# Interface_PCB.net
KiCad netlist of a schematic drawn in EAGLE
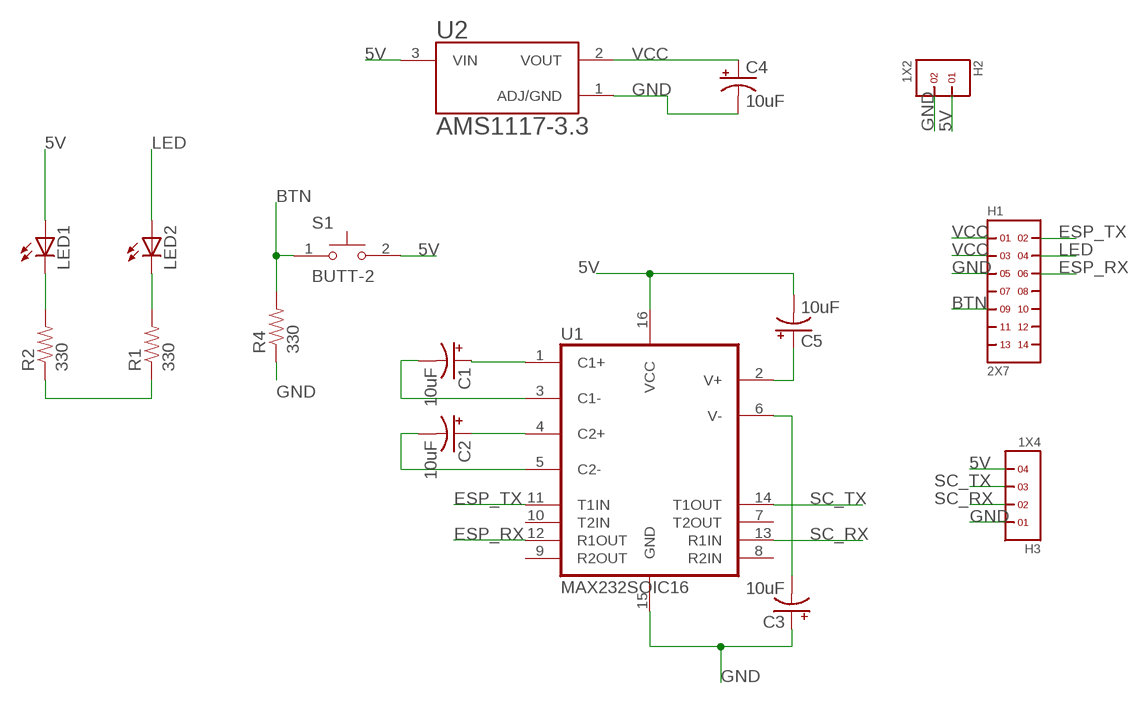
[diagram p0: schematic, sheet 1]

(export (version "E")
  (design (tool "Eeschema 10.0.6"))
  (components
    (comp (ref "C1")
      (value "10uF")
      (footprint "eagle-import:EIA3216")
      (libsource (lib "eagle-import") (part "10UF-16V-10%(TANT)"))
    )
    (comp (ref "C2")
      (value "10uF")
      (footprint "eagle-import:EIA3216")
      (libsource (lib "eagle-import") (part "10UF-16V-10%(TANT)"))
    )
    (comp (ref "C3")
      (value "10uF")
      (footprint "eagle-import:EIA3216")
      (libsource (lib "eagle-import") (part "10UF-16V-10%(TANT)"))
    )
    (comp (ref "C4")
      (value "10uF")
      (footprint "eagle-import:EIA3216")
      (libsource (lib "eagle-import") (part "10UF-16V-10%(TANT)"))
    )
    (comp (ref "C5")
      (value "10uF")
      (footprint "eagle-import:EIA3216")
      (libsource (lib "eagle-import") (part "10UF-16V-10%(TANT)"))
    )
    (comp (ref "H1")
      (value "2X7")
      (footprint "eagle-import:2X7")
      (libsource (lib "eagle-import") (part "2X7"))
    )
    (comp (ref "H2")
      (value "1X2")
      (footprint "eagle-import:1X2")
      (libsource (lib "eagle-import") (part "1X2"))
    )
    (comp (ref "H3")
      (value "1X4")
      (footprint "eagle-import:1X4")
      (libsource (lib "eagle-import") (part "1X4"))
    )
    (comp (ref "LED1")
      (value "LED5MM")
      (footprint "eagle-import:LED5MM")
      (libsource (lib "eagle-import") (part "LED5MM"))
    )
    (comp (ref "LED2")
      (value "LED5MM")
      (footprint "eagle-import:LED5MM")
      (libsource (lib "eagle-import") (part "LED5MM"))
    )
    (comp (ref "R1")
      (value "330")
      (footprint "eagle-import:0402-RES")
      (libsource (lib "eagle-import") (part "RESISTOR0402-RES"))
    )
    (comp (ref "R2")
      (value "330")
      (footprint "eagle-import:0402-RES")
      (libsource (lib "eagle-import") (part "RESISTOR0402-RES"))
    )
    (comp (ref "R4")
      (value "330")
      (footprint "eagle-import:0402-RES")
      (libsource (lib "eagle-import") (part "RESISTOR0402-RES"))
    )
    (comp (ref "S1")
      (value "BUTT-2")
      (footprint "eagle-import:SW_BUTT-2")
      (fields (field (name "MF") "Gravitech"))
      (libsource (lib "eagle-import") (part "BUTT-2"))
    )
    (comp (ref "U1")
      (value "MAX232SOIC16")
      (footprint "eagle-import:SO016")
      (libsource (lib "eagle-import") (part "MAX232SOIC16"))
    )
    (comp (ref "U2")
      (value "AMS1117-3.3")
      (footprint "eagle-import:SOT229P700X180-4N")
      (fields (field (name "MF") "Advanced Monolithic Systems"))
      (libsource (lib "eagle-import") (part "AMS1117-3.3"))
    )
  )
  (nets
    (net (code "1") (name "/5V") (class "Default")
      (node (ref "C5") (pin "C") (pinfunction "-_C") (pintype "passive"))
      (node (ref "H2") (pin "1") (pinfunction "1_1") (pintype "bidirectional"))
      (node (ref "H3") (pin "4") (pinfunction "4_4") (pintype "bidirectional"))
      (node (ref "LED1") (pin "A") (pinfunction "A_A") (pintype "passive"))
      (node (ref "S1") (pin "2") (pinfunction "2_2") (pintype "passive"))
      (node (ref "U1") (pin "16") (pinfunction "VCC_16") (pintype "bidirectional"))
      (node (ref "U2") (pin "3") (pinfunction "VIN_3") (pintype "input"))
    )
    (net (code "2") (name "/BTN") (class "Default")
      (node (ref "H1") (pin "9") (pinfunction "9_9") (pintype "bidirectional"))
      (node (ref "R4") (pin "2") (pinfunction "2_2") (pintype "passive"))
      (node (ref "S1") (pin "1") (pinfunction "1_1") (pintype "passive"))
    )
    (net (code "3") (name "/ESP_RX") (class "Default")
      (node (ref "H1") (pin "6") (pinfunction "6_6") (pintype "bidirectional"))
      (node (ref "U1") (pin "12") (pinfunction "R1OUT_12") (pintype "output"))
    )
    (net (code "4") (name "/ESP_TX") (class "Default")
      (node (ref "H1") (pin "2") (pinfunction "2_2") (pintype "bidirectional"))
      (node (ref "U1") (pin "11") (pinfunction "T1IN_11") (pintype "input"))
    )
    (net (code "5") (name "/GND") (class "Default")
      (node (ref "C3") (pin "A") (pinfunction "+_A") (pintype "passive"))
      (node (ref "C4") (pin "C") (pinfunction "-_C") (pintype "passive"))
      (node (ref "H1") (pin "5") (pinfunction "5_5") (pintype "bidirectional"))
      (node (ref "H2") (pin "2") (pinfunction "2_2") (pintype "bidirectional"))
      (node (ref "H3") (pin "1") (pinfunction "1_1") (pintype "bidirectional"))
      (node (ref "R4") (pin "1") (pinfunction "1_1") (pintype "passive"))
      (node (ref "U1") (pin "15") (pinfunction "GND_15") (pintype "bidirectional"))
      (node (ref "U2") (pin "1") (pinfunction "ADJ/GND_1") (pintype "power_in"))
    )
    (net (code "6") (name "/LED") (class "Default")
      (node (ref "H1") (pin "4") (pinfunction "4_4") (pintype "bidirectional"))
      (node (ref "LED2") (pin "A") (pinfunction "A_A") (pintype "passive"))
    )
    (net (code "7") (name "/SC_RX") (class "Default")
      (node (ref "H3") (pin "2") (pinfunction "2_2") (pintype "bidirectional"))
      (node (ref "U1") (pin "13") (pinfunction "R1IN_13") (pintype "input"))
    )
    (net (code "8") (name "/SC_TX") (class "Default")
      (node (ref "H3") (pin "3") (pinfunction "3_3") (pintype "bidirectional"))
      (node (ref "U1") (pin "14") (pinfunction "T1OUT_14") (pintype "output"))
    )
    (net (code "9") (name "/VCC") (class "Default")
      (node (ref "C4") (pin "A") (pinfunction "+_A") (pintype "passive"))
      (node (ref "H1") (pin "1") (pinfunction "1_1") (pintype "bidirectional"))
      (node (ref "H1") (pin "3") (pinfunction "3_3") (pintype "bidirectional"))
      (node (ref "U2") (pin "2") (pinfunction "VOUT_2") (pintype "output"))
    )
    (net (code "10") (name "Net-(C1-+)") (class "Default")
      (node (ref "C1") (pin "A") (pinfunction "+_A") (pintype "passive"))
      (node (ref "U1") (pin "1") (pinfunction "C1+_1") (pintype "bidirectional"))
    )
    (net (code "11") (name "Net-(C1--)") (class "Default")
      (node (ref "C1") (pin "C") (pinfunction "-_C") (pintype "passive"))
      (node (ref "U1") (pin "3") (pinfunction "C1-_3") (pintype "bidirectional"))
    )
    (net (code "12") (name "Net-(C2-+)") (class "Default")
      (node (ref "C2") (pin "A") (pinfunction "+_A") (pintype "passive"))
      (node (ref "U1") (pin "4") (pinfunction "C2+_4") (pintype "bidirectional"))
    )
    (net (code "13") (name "Net-(C2--)") (class "Default")
      (node (ref "C2") (pin "C") (pinfunction "-_C") (pintype "passive"))
      (node (ref "U1") (pin "5") (pinfunction "C2-_5") (pintype "bidirectional"))
    )
    (net (code "14") (name "Net-(C3--)") (class "Default")
      (node (ref "C3") (pin "C") (pinfunction "-_C") (pintype "passive"))
      (node (ref "U1") (pin "6") (pinfunction "V-_6") (pintype "bidirectional"))
    )
    (net (code "15") (name "Net-(C5-+)") (class "Default")
      (node (ref "C5") (pin "A") (pinfunction "+_A") (pintype "passive"))
      (node (ref "U1") (pin "2") (pinfunction "V+_2") (pintype "bidirectional"))
    )
    (net (code "16") (name "Net-(LED1-C)") (class "Default")
      (node (ref "LED1") (pin "K") (pinfunction "C_K") (pintype "passive"))
      (node (ref "R2") (pin "2") (pinfunction "2_2") (pintype "passive"))
    )
    (net (code "17") (name "Net-(LED2-C)") (class "Default")
      (node (ref "LED2") (pin "K") (pinfunction "C_K") (pintype "passive"))
      (node (ref "R1") (pin "2") (pinfunction "2_2") (pintype "passive"))
    )
    (net (code "18") (name "Net-(R1-Pad1)") (class "Default")
      (node (ref "R1") (pin "1") (pinfunction "1_1") (pintype "passive"))
      (node (ref "R2") (pin "1") (pinfunction "1_1") (pintype "passive"))
    )
    (net (code "19") (name "unconnected-(H1-Pad7)") (class "Default")
      (node (ref "H1") (pin "7") (pinfunction "7_7") (pintype "bidirectional"))
    )
    (net (code "20") (name "unconnected-(H1-Pad8)") (class "Default")
      (node (ref "H1") (pin "8") (pinfunction "8_8") (pintype "bidirectional"))
    )
    (net (code "21") (name "unconnected-(H1-Pad10)") (class "Default")
      (node (ref "H1") (pin "10") (pinfunction "10_10") (pintype "bidirectional"))
    )
    (net (code "22") (name "unconnected-(H1-Pad11)") (class "Default")
      (node (ref "H1") (pin "11") (pinfunction "11_11") (pintype "bidirectional"))
    )
    (net (code "23") (name "unconnected-(H1-Pad12)") (class "Default")
      (node (ref "H1") (pin "12") (pinfunction "12_12") (pintype "bidirectional"))
    )
    (net (code "24") (name "unconnected-(H1-Pad13)") (class "Default")
      (node (ref "H1") (pin "13") (pinfunction "13_13") (pintype "bidirectional"))
    )
    (net (code "25") (name "unconnected-(H1-Pad14)") (class "Default")
      (node (ref "H1") (pin "14") (pinfunction "14_14") (pintype "bidirectional"))
    )
    (net (code "26") (name "unconnected-(U1-R2IN-Pad8)") (class "Default")
      (node (ref "U1") (pin "8") (pinfunction "R2IN_8") (pintype "input"))
    )
    (net (code "27") (name "unconnected-(U1-R2OUT-Pad9)") (class "Default")
      (node (ref "U1") (pin "9") (pinfunction "R2OUT_9") (pintype "output"))
    )
    (net (code "28") (name "unconnected-(U1-T2IN-Pad10)") (class "Default")
      (node (ref "U1") (pin "10") (pinfunction "T2IN_10") (pintype "input"))
    )
    (net (code "29") (name "unconnected-(U1-T2OUT-Pad7)") (class "Default")
      (node (ref "U1") (pin "7") (pinfunction "T2OUT_7") (pintype "output"))
    )
  )
)
